# Cymometer.net
KiCad netlist of a schematic drawn in Altium Designer
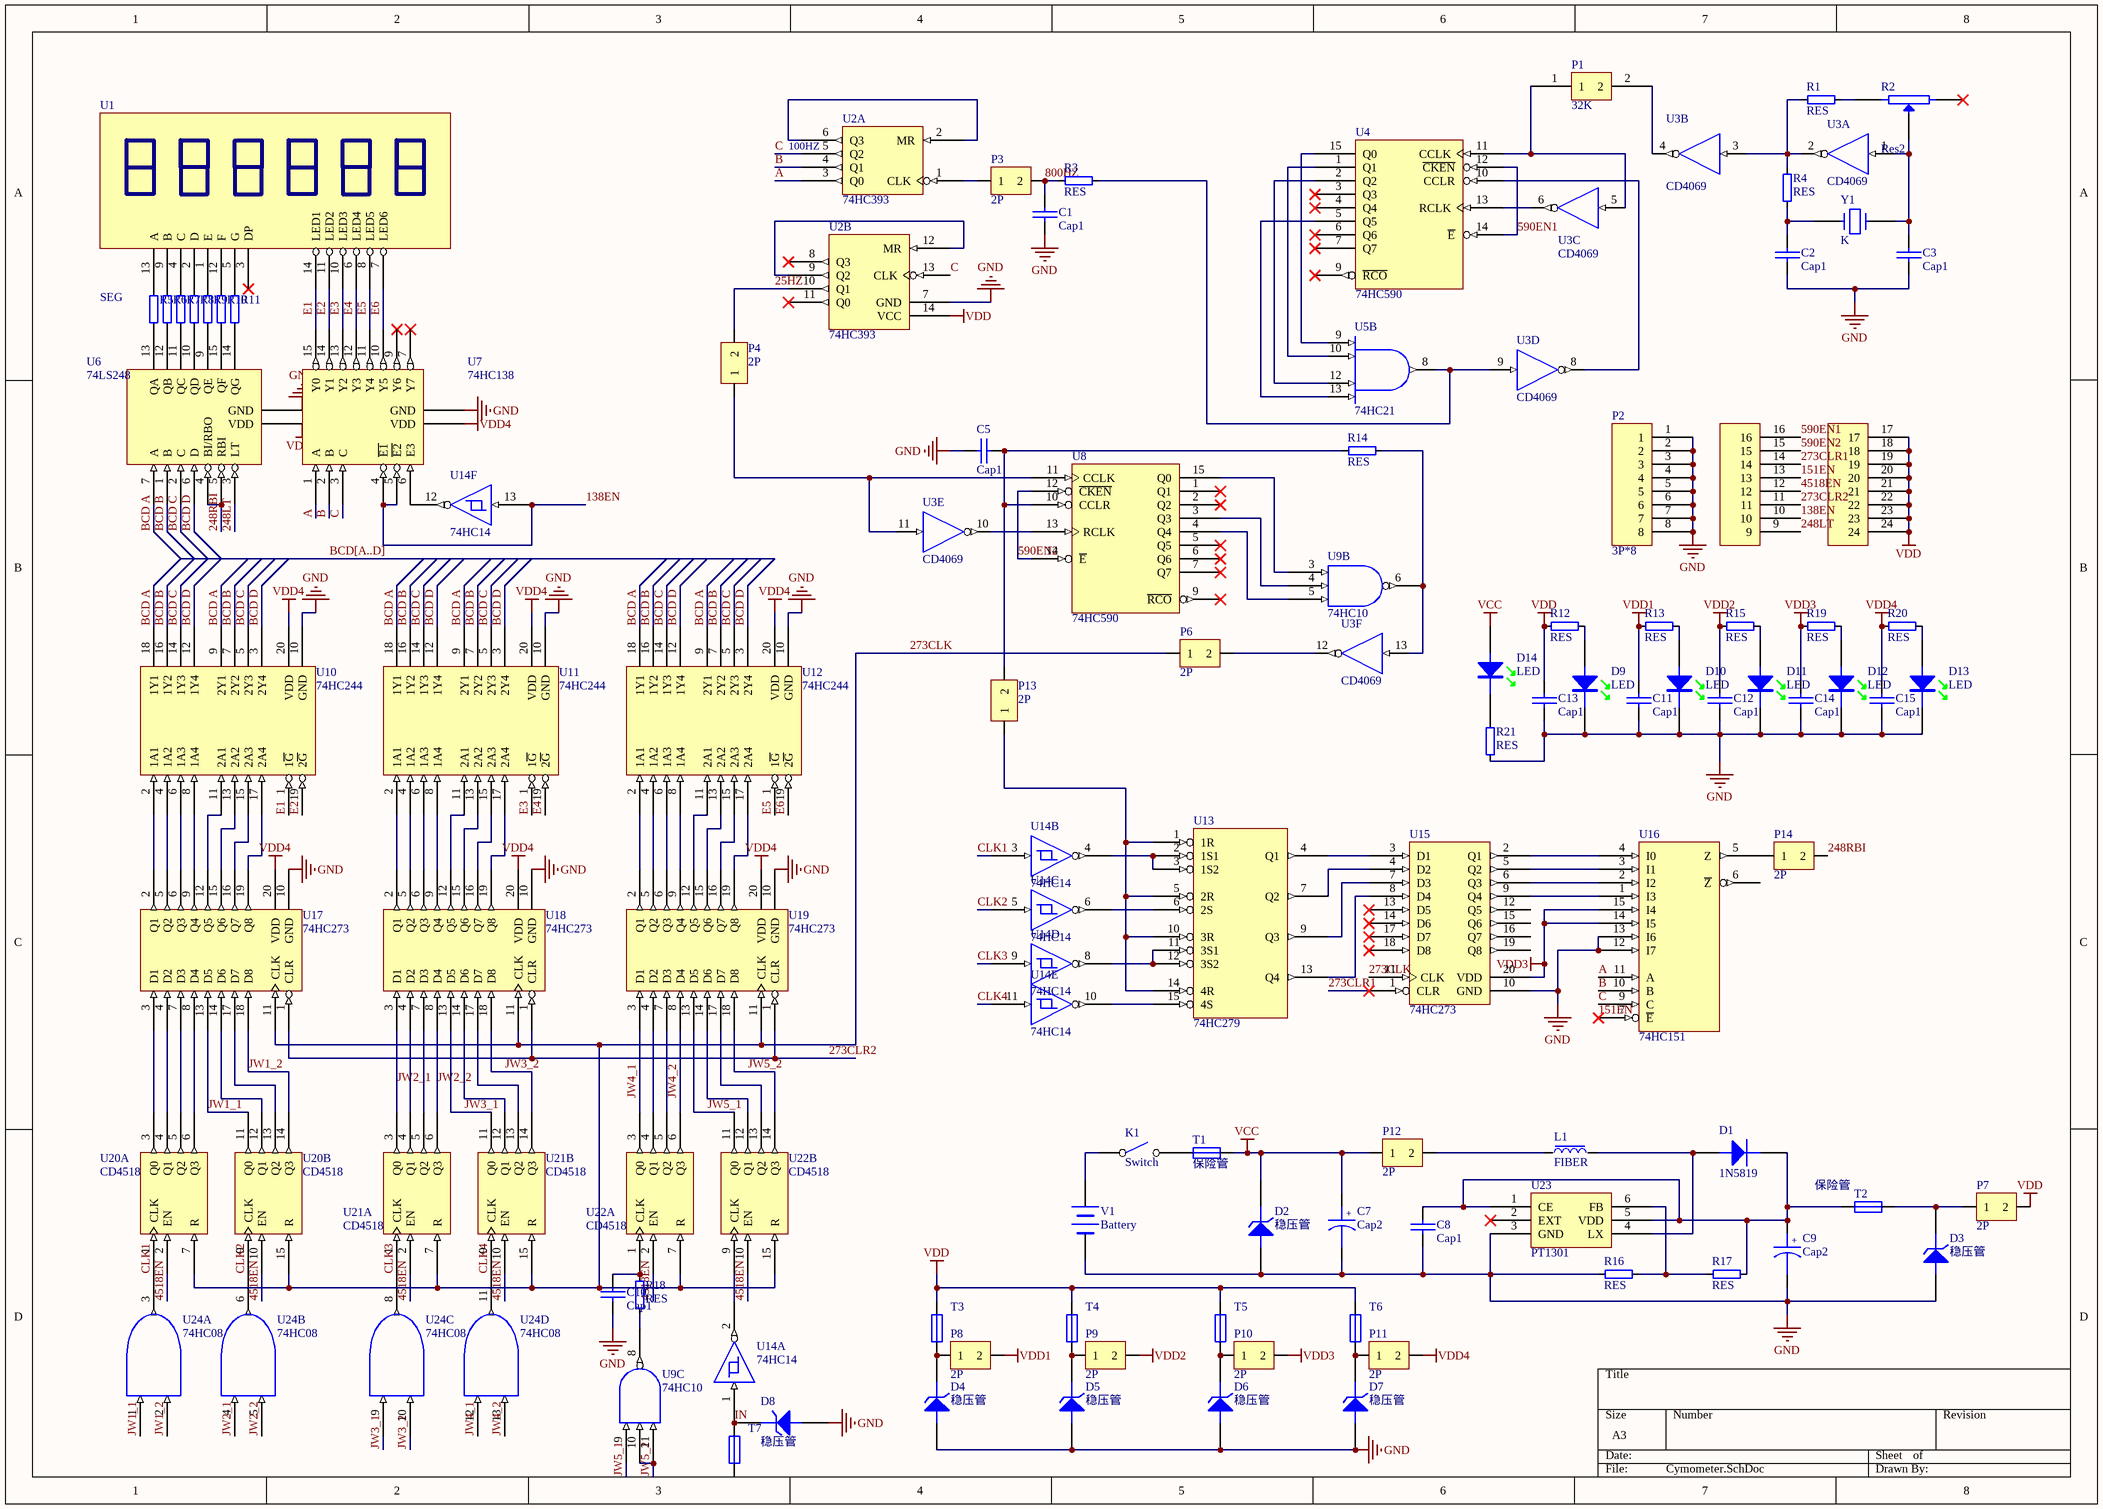
[diagram p0: Cymometer.SchDoc]

(export (version "E")
  (design (tool "Eeschema 10.0.6"))
  (components
    (comp (ref "C1") (value "Cap1") (footprint "Cap1") (libsource (lib "Cymometer") (part "Cap1")))
    (comp (ref "C2") (value "Cap1") (footprint "Cap1") (libsource (lib "Cymometer") (part "Cap1")))
    (comp (ref "C3") (value "Cap1") (footprint "Cap1") (libsource (lib "Cymometer") (part "Cap1")))
    (comp (ref "C5") (value "Cap1") (footprint "Cap1") (libsource (lib "Cymometer") (part "Cap1")))
    (comp (ref "C7") (value "Cap2") (footprint "Cap2") (libsource (lib "Cymometer") (part "Cap2")))
    (comp (ref "C8") (value "Cap1") (footprint "Cap1") (libsource (lib "Cymometer") (part "Cap1")))
    (comp (ref "C9") (value "Cap2") (footprint "Cap2") (libsource (lib "Cymometer") (part "Cap2")))
    (comp (ref "C10") (value "Cap1") (footprint "Cap1") (libsource (lib "Cymometer") (part "Cap1")))
    (comp (ref "C11") (value "Cap1") (footprint "Cap1") (libsource (lib "Cymometer") (part "Cap1")))
    (comp (ref "C12") (value "Cap1") (footprint "Cap1") (libsource (lib "Cymometer") (part "Cap1")))
    (comp (ref "C13") (value "Cap1") (footprint "Cap1") (libsource (lib "Cymometer") (part "Cap1")))
    (comp (ref "C14") (value "Cap1") (footprint "Cap1") (libsource (lib "Cymometer") (part "Cap1")))
    (comp (ref "C15") (value "Cap1") (footprint "Cap1") (libsource (lib "Cymometer") (part "Cap1")))
    (comp (ref "D1") (value "1N5819") (footprint "1N5819(SMA)") (libsource (lib "Cymometer") (part "1N5819")))
    (comp (ref "D2") (value "稳压管") (footprint "1206稳压管") (libsource (lib "Cymometer") (part "稳压管")))
    (comp (ref "D3") (value "稳压管") (footprint "1206稳压管") (libsource (lib "Cymometer") (part "稳压管")))
    (comp (ref "D4") (value "稳压管") (footprint "1206稳压管") (libsource (lib "Cymometer") (part "稳压管")))
    (comp (ref "D5") (value "稳压管") (footprint "1206稳压管") (libsource (lib "Cymometer") (part "稳压管")))
    (comp (ref "D6") (value "稳压管") (footprint "1206稳压管") (libsource (lib "Cymometer") (part "稳压管")))
    (comp (ref "D7") (value "稳压管") (footprint "1206稳压管") (libsource (lib "Cymometer") (part "稳压管")))
    (comp (ref "D8") (value "稳压管") (footprint "1206稳压管") (libsource (lib "Cymometer") (part "稳压管")))
    (comp (ref "D9") (value "LED") (footprint "0805LED") (libsource (lib "Cymometer") (part "LED")))
    (comp (ref "D10") (value "LED") (footprint "0805LED") (libsource (lib "Cymometer") (part "LED")))
    (comp (ref "D11") (value "LED") (footprint "0805LED") (libsource (lib "Cymometer") (part "LED")))
    (comp (ref "D12") (value "LED") (footprint "0805LED") (libsource (lib "Cymometer") (part "LED")))
    (comp (ref "D13") (value "LED") (footprint "0805LED") (libsource (lib "Cymometer") (part "LED")))
    (comp (ref "D14") (value "LED") (footprint "0805LED") (libsource (lib "Cymometer") (part "LED")))
    (comp (ref "K1") (value "Switch") (footprint "Switch") (libsource (lib "Cymometer") (part "Switch")))
    (comp (ref "L1") (value "FIBER") (footprint "FIBER") (libsource (lib "Cymometer") (part "FIBER")))
    (comp (ref "P1") (value "32K") (footprint "2P") (libsource (lib "") (part "2P_2")))
    (comp (ref "P2") (value "3P*8") (footprint "3P*8") (libsource (lib "Cymometer") (part "3P*8")))
    (comp (ref "P3") (value "2P") (footprint "2P") (libsource (lib "Cymometer") (part "2P")))
    (comp (ref "P4") (value "2P") (footprint "2P") (libsource (lib "") (part "2P_1")))
    (comp (ref "P6") (value "2P") (footprint "2P") (libsource (lib "Cymometer") (part "2P")))
    (comp (ref "P7") (value "2P") (footprint "2P") (libsource (lib "Cymometer") (part "2P")))
    (comp (ref "P8") (value "2P") (footprint "2P") (libsource (lib "Cymometer") (part "2P")))
    (comp (ref "P9") (value "2P") (footprint "2P") (libsource (lib "Cymometer") (part "2P")))
    (comp (ref "P10") (value "2P") (footprint "2P") (libsource (lib "Cymometer") (part "2P")))
    (comp (ref "P11") (value "2P") (footprint "2P") (libsource (lib "Cymometer") (part "2P")))
    (comp (ref "P12") (value "2P") (footprint "2P") (libsource (lib "Cymometer") (part "2P")))
    (comp (ref "P13") (value "2P") (footprint "2P") (libsource (lib "") (part "2P_1")))
    (comp (ref "P14") (value "2P") (footprint "2P") (libsource (lib "Cymometer") (part "2P")))
    (comp (ref "R1")
      (value "RES")
      (footprint "0805R")
      (description "电阻")
      (libsource (lib "Cymometer") (part "RES"))
    )
    (comp (ref "R2") (value "Res2") (footprint "Res2") (libsource (lib "Cymometer") (part "Res2")))
    (comp (ref "R3")
      (value "RES")
      (footprint "0805R")
      (description "电阻")
      (libsource (lib "Cymometer") (part "RES"))
    )
    (comp (ref "R4")
      (value "RES")
      (footprint "0805R")
      (description "电阻")
      (libsource (lib "Cymometer") (part "RES"))
    )
    (comp (ref "R5")
      (value "~")
      (footprint "0805R")
      (description "电阻")
      (libsource (lib "Cymometer") (part "RES"))
    )
    (comp (ref "R6")
      (value "~")
      (footprint "0805R")
      (description "电阻")
      (libsource (lib "Cymometer") (part "RES"))
    )
    (comp (ref "R7")
      (value "~")
      (footprint "0805R")
      (description "电阻")
      (libsource (lib "Cymometer") (part "RES"))
    )
    (comp (ref "R8")
      (value "~")
      (footprint "0805R")
      (description "电阻")
      (libsource (lib "Cymometer") (part "RES"))
    )
    (comp (ref "R9")
      (value "~")
      (footprint "0805R")
      (description "电阻")
      (libsource (lib "Cymometer") (part "RES"))
    )
    (comp (ref "R10")
      (value "~")
      (footprint "0805R")
      (description "电阻")
      (libsource (lib "Cymometer") (part "RES"))
    )
    (comp (ref "R11")
      (value "~")
      (footprint "0805R")
      (description "电阻")
      (libsource (lib "Cymometer") (part "RES"))
    )
    (comp (ref "R12")
      (value "RES")
      (footprint "0805R")
      (description "电阻")
      (libsource (lib "Cymometer") (part "RES"))
    )
    (comp (ref "R13")
      (value "RES")
      (footprint "0805R")
      (description "电阻")
      (libsource (lib "Cymometer") (part "RES"))
    )
    (comp (ref "R14")
      (value "RES")
      (footprint "0805R")
      (description "电阻")
      (libsource (lib "Cymometer") (part "RES"))
    )
    (comp (ref "R15")
      (value "RES")
      (footprint "0805R")
      (description "电阻")
      (libsource (lib "Cymometer") (part "RES"))
    )
    (comp (ref "R16")
      (value "RES")
      (footprint "0805R")
      (description "电阻")
      (libsource (lib "Cymometer") (part "RES"))
    )
    (comp (ref "R17")
      (value "RES")
      (footprint "0805R")
      (description "电阻")
      (libsource (lib "Cymometer") (part "RES"))
    )
    (comp (ref "R18")
      (value "RES")
      (footprint "0805R")
      (description "电阻")
      (libsource (lib "Cymometer") (part "RES"))
    )
    (comp (ref "R19")
      (value "RES")
      (footprint "0805R")
      (description "电阻")
      (libsource (lib "Cymometer") (part "RES"))
    )
    (comp (ref "R20")
      (value "RES")
      (footprint "0805R")
      (description "电阻")
      (libsource (lib "Cymometer") (part "RES"))
    )
    (comp (ref "R21")
      (value "RES")
      (footprint "0805R")
      (description "电阻")
      (libsource (lib "Cymometer") (part "RES"))
    )
    (comp (ref "T1") (value "保险管") (footprint "0805T") (libsource (lib "") (part "保险管_1")))
    (comp (ref "T2") (value "保险管") (footprint "0805T") (libsource (lib "") (part "保险管_1")))
    (comp (ref "T3") (value "保险管") (footprint "0805T") (libsource (lib "") (part "保险管_2")))
    (comp (ref "T4") (value "保险管") (footprint "0805T") (libsource (lib "Cymometer") (part "保险管")))
    (comp (ref "T5") (value "保险管") (footprint "0805T") (libsource (lib "") (part "保险管_2")))
    (comp (ref "T6") (value "保险管") (footprint "0805T") (libsource (lib "Cymometer") (part "保险管")))
    (comp (ref "T7") (value "保险管") (footprint "0805T") (libsource (lib "") (part "保险管_2")))
    (comp (ref "U1")
      (value "SEG")
      (footprint "6BIT_SEG")
      (description "数码管")
      (libsource (lib "Cymometer") (part "SEG"))
    )
    (comp (ref "U2") (value "74HC393") (footprint "SOP14") (libsource (lib "Cymometer") (part "74HC393")))
    (comp (ref "U3")
      (value "CD4069")
      (footprint "DIP14")
      (description "CMOS非门")
      (libsource (lib "Cymometer") (part "CD4069"))
    )
    (comp (ref "U4") (value "74HC590") (footprint "SOP16") (libsource (lib "Cymometer") (part "74HC590")))
    (comp (ref "U5")
      (value "74HC21")
      (footprint "SOP14")
      (description "4输入与门")
      (libsource (lib "Cymometer") (part "74HC21"))
    )
    (comp (ref "U6")
      (value "74LS248")
      (footprint "DIP16")
      (description "数码管译码器")
      (libsource (lib "Cymometer") (part "74LS248"))
    )
    (comp (ref "U7")
      (value "74HC138")
      (footprint "SOP16")
      (description "38译码器")
      (libsource (lib "Cymometer") (part "74HC138"))
    )
    (comp (ref "U8") (value "74HC590") (footprint "SOP16") (libsource (lib "") (part "74HC590_1")))
    (comp (ref "U9") (value "74HC10") (footprint "SOP14") (libsource (lib "Cymometer") (part "74HC10")))
    (comp (ref "U10")
      (value "74HC244")
      (footprint "SOP20")
      (description "三态缓冲器")
      (libsource (lib "Cymometer") (part "74HC244"))
    )
    (comp (ref "U11")
      (value "74HC244")
      (footprint "SOP20")
      (description "三态缓冲器")
      (libsource (lib "Cymometer") (part "74HC244"))
    )
    (comp (ref "U12")
      (value "74HC244")
      (footprint "SOP20")
      (description "三态缓冲器")
      (libsource (lib "Cymometer") (part "74HC244"))
    )
    (comp (ref "U13") (value "74HC279") (footprint "DIP16") (libsource (lib "Cymometer") (part "74HC279")))
    (comp (ref "U14") (value "74HC14") (footprint "SOP14") (libsource (lib "Cymometer") (part "74HC14")))
    (comp (ref "U15")
      (value "74HC273")
      (footprint "SOP20")
      (description "D触发器")
      (libsource (lib "") (part "74HC273_1"))
    )
    (comp (ref "U16") (value "74HC151") (footprint "DIP16") (libsource (lib "Cymometer") (part "74HC151")))
    (comp (ref "U17")
      (value "74HC273")
      (footprint "SOP20")
      (description "D触发器")
      (libsource (lib "Cymometer") (part "74HC273"))
    )
    (comp (ref "U18")
      (value "74HC273")
      (footprint "SOP20")
      (description "D触发器")
      (libsource (lib "Cymometer") (part "74HC273"))
    )
    (comp (ref "U19")
      (value "74HC273")
      (footprint "SOP20")
      (description "D触发器")
      (libsource (lib "Cymometer") (part "74HC273"))
    )
    (comp (ref "U20")
      (value "CD4518")
      (footprint "DIP16")
      (description "BCD计数器")
      (libsource (lib "Cymometer") (part "CD4518"))
    )
    (comp (ref "U21")
      (value "CD4518")
      (footprint "DIP16")
      (description "BCD计数器")
      (libsource (lib "") (part "CD4518_1"))
    )
    (comp (ref "U22")
      (value "CD4518")
      (footprint "DIP16")
      (description "BCD计数器")
      (libsource (lib "") (part "CD4518_1"))
    )
    (comp (ref "U23") (value "PT1301") (footprint "Sop26") (libsource (lib "Cymometer") (part "PT1301")))
    (comp (ref "U24")
      (value "74HC08")
      (footprint "SOP14")
      (description "二输入与门")
      (libsource (lib "Cymometer") (part "74HC08"))
    )
    (comp (ref "V1") (value "Battery") (footprint "Battry") (libsource (lib "Cymometer") (part "Battery")))
    (comp (ref "Y1")
      (value "K")
      (footprint "CRYSTAL")
      (description "晶振")
      (libsource (lib "Cymometer") (part "CRYSTAL"))
    )
  )
  (nets
    (net (code "2") (name "/25HZ") (class "Default")
      (node (ref "P4") (pin "2") (pinfunction "2_2") (pintype "passive"))
      (node (ref "U2") (pin "10") (pinfunction "Q1_10") (pintype "output"))
    )
    (net (code "3") (name "/138EN") (class "Default")
      (node (ref "P2") (pin "10") (pinfunction "10_10") (pintype "passive"))
      (node (ref "U14") (pin "13") (pintype "input"))
      (node (ref "U7") (pin "4") (pinfunction "~{E1}_4") (pintype "input"))
      (node (ref "U7") (pin "5") (pinfunction "~{E2}_5") (pintype "input"))
    )
    (net (code "4") (name "/151EN") (class "Default")
      (node (ref "P2") (pin "13") (pinfunction "13_13") (pintype "passive"))
      (node (ref "U16") (pin "7") (pinfunction "~{E}_7") (pintype "input"))
    )
    (net (code "5") (name "/248LT") (class "Default")
      (node (ref "P2") (pin "9") (pinfunction "9_9") (pintype "passive"))
      (node (ref "U6") (pin "3") (pinfunction "LT_3") (pintype "input"))
    )
    (net (code "6") (name "/248RBI") (class "Default")
      (node (ref "P14") (pin "2") (pinfunction "2_2") (pintype "passive"))
      (node (ref "U6") (pin "4") (pinfunction "BI/RBO_4") (pintype "input"))
      (node (ref "U6") (pin "5") (pinfunction "RBI_5") (pintype "input"))
    )
    (net (code "7") (name "/273CLK") (class "Default")
      (node (ref "P6") (pin "1") (pinfunction "1_1") (pintype "passive"))
      (node (ref "U15") (pin "11") (pinfunction "CLK_11") (pintype "input"))
      (node (ref "U17") (pin "11") (pinfunction "CLK_11") (pintype "input"))
      (node (ref "U18") (pin "11") (pinfunction "CLK_11") (pintype "input"))
      (node (ref "U19") (pin "11") (pinfunction "CLK_11") (pintype "input"))
      (node (ref "U20") (pin "15") (pinfunction "R_15") (pintype "input"))
      (node (ref "U20") (pin "7") (pinfunction "R_7") (pintype "input"))
      (node (ref "U21") (pin "15") (pinfunction "R_15") (pintype "input"))
      (node (ref "U21") (pin "7") (pinfunction "R_7") (pintype "input"))
      (node (ref "U22") (pin "15") (pinfunction "R_15") (pintype "input"))
      (node (ref "U22") (pin "7") (pinfunction "R_7") (pintype "input"))
    )
    (net (code "8") (name "/273CLR1") (class "Default")
      (node (ref "P2") (pin "14") (pinfunction "14_14") (pintype "passive"))
      (node (ref "U15") (pin "1") (pinfunction "CLR_1") (pintype "input"))
    )
    (net (code "9") (name "/273CLR2") (class "Default")
      (node (ref "P2") (pin "11") (pinfunction "11_11") (pintype "passive"))
      (node (ref "U17") (pin "1") (pinfunction "CLR_1") (pintype "input"))
      (node (ref "U18") (pin "1") (pinfunction "CLR_1") (pintype "input"))
      (node (ref "U19") (pin "1") (pinfunction "CLR_1") (pintype "input"))
    )
    (net (code "10") (name "/590EN1") (class "Default")
      (node (ref "P2") (pin "16") (pinfunction "16_16") (pintype "passive"))
      (node (ref "U4") (pin "12") (pinfunction "~{CKEN}_12") (pintype "input"))
      (node (ref "U4") (pin "14") (pinfunction "~{E}_14") (pintype "input"))
    )
    (net (code "11") (name "/590EN2") (class "Default")
      (node (ref "P2") (pin "15") (pinfunction "15_15") (pintype "passive"))
      (node (ref "U8") (pin "12") (pinfunction "~{CKEN}_12") (pintype "input"))
      (node (ref "U8") (pin "14") (pinfunction "~{E}_14") (pintype "input"))
    )
    (net (code "12") (name "/800HZ") (class "Default")
      (node (ref "C1") (pin "2") (pinfunction "2_2") (pintype "passive"))
      (node (ref "P3") (pin "2") (pinfunction "2_2") (pintype "passive"))
      (node (ref "R3") (pin "1") (pinfunction "1_1") (pintype "passive"))
    )
    (net (code "13") (name "/4518EN") (class "Default")
      (node (ref "P2") (pin "12") (pinfunction "12_12") (pintype "passive"))
      (node (ref "U20") (pin "10") (pinfunction "EN_10") (pintype "input"))
      (node (ref "U20") (pin "2") (pinfunction "EN_2") (pintype "input"))
      (node (ref "U21") (pin "10") (pinfunction "EN_10") (pintype "input"))
      (node (ref "U21") (pin "2") (pinfunction "EN_2") (pintype "input"))
      (node (ref "U22") (pin "10") (pinfunction "EN_10") (pintype "input"))
      (node (ref "U22") (pin "2") (pinfunction "EN_2") (pintype "input"))
    )
    (net (code "14") (name "/A") (class "Default")
      (node (ref "U16") (pin "11") (pinfunction "A_11") (pintype "input"))
      (node (ref "U2") (pin "3") (pinfunction "Q0_3") (pintype "output"))
      (node (ref "U7") (pin "1") (pinfunction "A_1") (pintype "input"))
    )
    (net (code "15") (name "/B") (class "Default")
      (node (ref "U16") (pin "10") (pinfunction "B_10") (pintype "input"))
      (node (ref "U2") (pin "4") (pinfunction "Q1_4") (pintype "output"))
      (node (ref "U7") (pin "2") (pinfunction "B_2") (pintype "input"))
    )
    (net (code "16") (name "/BCD A") (class "Default")
      (node (ref "U10") (pin "18") (pinfunction "1Y1_18") (pintype "tri_state"))
      (node (ref "U10") (pin "9") (pinfunction "2Y1_9") (pintype "tri_state"))
      (node (ref "U11") (pin "18") (pinfunction "1Y1_18") (pintype "tri_state"))
      (node (ref "U11") (pin "9") (pinfunction "2Y1_9") (pintype "tri_state"))
      (node (ref "U12") (pin "18") (pinfunction "1Y1_18") (pintype "tri_state"))
      (node (ref "U12") (pin "9") (pinfunction "2Y1_9") (pintype "tri_state"))
      (node (ref "U6") (pin "7") (pinfunction "A_7") (pintype "input"))
    )
    (net (code "17") (name "/BCD B") (class "Default")
      (node (ref "U10") (pin "16") (pinfunction "1Y2_16") (pintype "tri_state"))
      (node (ref "U10") (pin "7") (pinfunction "2Y2_7") (pintype "tri_state"))
      (node (ref "U11") (pin "16") (pinfunction "1Y2_16") (pintype "tri_state"))
      (node (ref "U11") (pin "7") (pinfunction "2Y2_7") (pintype "tri_state"))
      (node (ref "U12") (pin "16") (pinfunction "1Y2_16") (pintype "tri_state"))
      (node (ref "U12") (pin "7") (pinfunction "2Y2_7") (pintype "tri_state"))
      (node (ref "U6") (pin "1") (pinfunction "B_1") (pintype "input"))
    )
    (net (code "18") (name "/BCD C") (class "Default")
      (node (ref "U10") (pin "14") (pinfunction "1Y3_14") (pintype "tri_state"))
      (node (ref "U10") (pin "5") (pinfunction "2Y3_5") (pintype "tri_state"))
      (node (ref "U11") (pin "14") (pinfunction "1Y3_14") (pintype "tri_state"))
      (node (ref "U11") (pin "5") (pinfunction "2Y3_5") (pintype "tri_state"))
      (node (ref "U12") (pin "14") (pinfunction "1Y3_14") (pintype "tri_state"))
      (node (ref "U12") (pin "5") (pinfunction "2Y3_5") (pintype "tri_state"))
      (node (ref "U6") (pin "2") (pinfunction "C_2") (pintype "input"))
    )
    (net (code "19") (name "/BCD D") (class "Default")
      (node (ref "U10") (pin "12") (pinfunction "1Y4_12") (pintype "tri_state"))
      (node (ref "U10") (pin "3") (pinfunction "2Y4_3") (pintype "tri_state"))
      (node (ref "U11") (pin "12") (pinfunction "1Y4_12") (pintype "tri_state"))
      (node (ref "U11") (pin "3") (pinfunction "2Y4_3") (pintype "tri_state"))
      (node (ref "U12") (pin "12") (pinfunction "1Y4_12") (pintype "tri_state"))
      (node (ref "U12") (pin "3") (pinfunction "2Y4_3") (pintype "tri_state"))
      (node (ref "U6") (pin "6") (pinfunction "D_6") (pintype "input"))
    )
    (net (code "20") (name "/C") (class "Default")
      (node (ref "U16") (pin "9") (pinfunction "C_9") (pintype "input"))
      (node (ref "U2") (pin "13") (pinfunction "CLK_13") (pintype "input"))
      (node (ref "U2") (pin "5") (pinfunction "Q2_5") (pintype "output"))
      (node (ref "U7") (pin "3") (pinfunction "C_3") (pintype "input"))
    )
    (net (code "21") (name "/CLK1") (class "Default")
      (node (ref "U14") (pin "3") (pintype "input"))
      (node (ref "U20") (pin "1") (pinfunction "CLK_1") (pintype "input"))
      (node (ref "U24") (pin "3") (pintype "output"))
    )
    (net (code "22") (name "/CLK2") (class "Default")
      (node (ref "U14") (pin "5") (pintype "input"))
      (node (ref "U20") (pin "9") (pinfunction "CLK_9") (pintype "input"))
      (node (ref "U24") (pin "6") (pintype "output"))
    )
    (net (code "23") (name "/CLK3") (class "Default")
      (node (ref "U14") (pin "9") (pintype "input"))
      (node (ref "U21") (pin "1") (pinfunction "CLK_1") (pintype "input"))
      (node (ref "U24") (pin "8") (pintype "output"))
    )
    (net (code "24") (name "/CLK4") (class "Default")
      (node (ref "U14") (pin "11") (pintype "input"))
      (node (ref "U21") (pin "9") (pinfunction "CLK_9") (pintype "input"))
      (node (ref "U24") (pin "11") (pintype "output"))
    )
    (net (code "25") (name "/E1") (class "Default")
      (node (ref "U1") (pin "14") (pinfunction "LED1_14") (pintype "passive"))
      (node (ref "U10") (pin "1") (pinfunction "1~{G}_1") (pintype "input"))
      (node (ref "U7") (pin "15") (pinfunction "Y0_15") (pintype "output"))
    )
    (net (code "26") (name "/E2") (class "Default")
      (node (ref "U1") (pin "11") (pinfunction "LED2_11") (pintype "passive"))
      (node (ref "U10") (pin "19") (pinfunction "2~{G}_19") (pintype "input"))
      (node (ref "U7") (pin "14") (pinfunction "Y1_14") (pintype "output"))
    )
    (net (code "27") (name "/E3") (class "Default")
      (node (ref "U1") (pin "10") (pinfunction "LED3_10") (pintype "passive"))
      (node (ref "U11") (pin "1") (pinfunction "1~{G}_1") (pintype "input"))
      (node (ref "U7") (pin "13") (pinfunction "Y2_13") (pintype "output"))
    )
    (net (code "28") (name "/E4") (class "Default")
      (node (ref "U1") (pin "6") (pinfunction "LED4_6") (pintype "passive"))
      (node (ref "U11") (pin "19") (pinfunction "2~{G}_19") (pintype "input"))
      (node (ref "U7") (pin "12") (pinfunction "Y3_12") (pintype "output"))
    )
    (net (code "29") (name "/E5") (class "Default")
      (node (ref "U1") (pin "8") (pinfunction "LED5_8") (pintype "passive"))
      (node (ref "U12") (pin "1") (pinfunction "1~{G}_1") (pintype "input"))
      (node (ref "U7") (pin "11") (pinfunction "Y4_11") (pintype "output"))
    )
    (net (code "30") (name "/E6") (class "Default")
      (node (ref "U1") (pin "7") (pinfunction "LED6_7") (pintype "passive"))
      (node (ref "U12") (pin "19") (pinfunction "2~{G}_19") (pintype "input"))
      (node (ref "U7") (pin "10") (pinfunction "Y5_10") (pintype "output"))
    )
    (net (code "31") (name "/IN") (class "Default")
      (node (ref "D8") (pin "K") (pinfunction "K_K") (pintype "passive"))
      (node (ref "T7") (pin "1") (pinfunction "1_1") (pintype "passive"))
      (node (ref "U14") (pin "1") (pintype "input"))
    )
    (net (code "32") (name "/JW1_1") (class "Default")
      (node (ref "U17") (pin "13") (pinfunction "D5_13") (pintype "input"))
      (node (ref "U20") (pin "11") (pinfunction "Q0_11") (pintype "output"))
      (node (ref "U24") (pin "1") (pintype "input"))
    )
    (net (code "33") (name "/JW1_2") (class "Default")
      (node (ref "U17") (pin "18") (pinfunction "D8_18") (pintype "input"))
      (node (ref "U20") (pin "14") (pinfunction "Q3_14") (pintype "output"))
      (node (ref "U24") (pin "2") (pintype "input"))
    )
    (net (code "34") (name "/JW2_1") (class "Default")
      (node (ref "U18") (pin "3") (pinfunction "D1_3") (pintype "input"))
      (node (ref "U21") (pin "3") (pinfunction "Q0_3") (pintype "output"))
      (node (ref "U24") (pin "4") (pintype "input"))
    )
    (net (code "35") (name "/JW2_2") (class "Default")
      (node (ref "U18") (pin "8") (pinfunction "D4_8") (pintype "input"))
      (node (ref "U21") (pin "6") (pinfunction "Q3_6") (pintype "output"))
      (node (ref "U24") (pin "5") (pintype "input"))
    )
    (net (code "36") (name "/JW3_1") (class "Default")
      (node (ref "U18") (pin "13") (pinfunction "D5_13") (pintype "input"))
      (node (ref "U21") (pin "11") (pinfunction "Q0_11") (pintype "output"))
      (node (ref "U24") (pin "9") (pintype "input"))
    )
    (net (code "37") (name "/JW3_2") (class "Default")
      (node (ref "U18") (pin "18") (pinfunction "D8_18") (pintype "input"))
      (node (ref "U21") (pin "14") (pinfunction "Q3_14") (pintype "output"))
      (node (ref "U24") (pin "10") (pintype "input"))
    )
    (net (code "38") (name "/JW4_1") (class "Default")
      (node (ref "U19") (pin "3") (pinfunction "D1_3") (pintype "input"))
      (node (ref "U22") (pin "3") (pinfunction "Q0_3") (pintype "output"))
      (node (ref "U24") (pin "12") (pintype "input"))
    )
    (net (code "39") (name "/JW4_2") (class "Default")
      (node (ref "U19") (pin "8") (pinfunction "D4_8") (pintype "input"))
      (node (ref "U22") (pin "6") (pinfunction "Q3_6") (pintype "output"))
      (node (ref "U24") (pin "13") (pintype "input"))
    )
    (net (code "40") (name "/JW5_1") (class "Default")
      (node (ref "U19") (pin "13") (pinfunction "D5_13") (pintype "input"))
      (node (ref "U22") (pin "11") (pinfunction "Q0_11") (pintype "output"))
      (node (ref "U9") (pin "9") (pintype "input"))
    )
    (net (code "41") (name "/JW5_2") (class "Default")
      (node (ref "U19") (pin "18") (pinfunction "D8_18") (pintype "input"))
      (node (ref "U22") (pin "14") (pinfunction "Q3_14") (pintype "output"))
      (node (ref "U9") (pin "10") (pintype "input"))
      (node (ref "U9") (pin "11") (pintype "input"))
    )
    (net (code "43") (name "GND") (class "Default")
      (node (ref "C1") (pin "1") (pinfunction "1_1") (pintype "passive"))
      (node (ref "C10") (pin "1") (pinfunction "1_1") (pintype "passive"))
      (node (ref "C11") (pin "1") (pinfunction "1_1") (pintype "passive"))
      (node (ref "C12") (pin "1") (pinfunction "1_1") (pintype "passive"))
      (node (ref "C13") (pin "1") (pinfunction "1_1") (pintype "passive"))
      (node (ref "C14") (pin "1") (pinfunction "1_1") (pintype "passive"))
      (node (ref "C15") (pin "1") (pinfunction "1_1") (pintype "passive"))
      (node (ref "C2") (pin "1") (pinfunction "1_1") (pintype "passive"))
      (node (ref "C3") (pin "1") (pinfunction "1_1") (pintype "passive"))
      (node (ref "C5") (pin "2") (pinfunction "2_2") (pintype "passive"))
      (node (ref "C7") (pin "K") (pinfunction "2_K") (pintype "passive"))
      (node (ref "C8") (pin "1") (pinfunction "1_1") (pintype "passive"))
      (node (ref "C9") (pin "K") (pinfunction "2_K") (pintype "passive"))
      (node (ref "D10") (pin "K") (pinfunction "2_K") (pintype "passive"))
      (node (ref "D11") (pin "K") (pinfunction "2_K") (pintype "passive"))
      (node (ref "D12") (pin "K") (pinfunction "2_K") (pintype "passive"))
      (node (ref "D13") (pin "K") (pinfunction "2_K") (pintype "passive"))
      (node (ref "D2") (pin "A") (pinfunction "A_A") (pintype "passive"))
      (node (ref "D3") (pin "A") (pinfunction "A_A") (pintype "passive"))
      (node (ref "D4") (pin "A") (pinfunction "A_A") (pintype "passive"))
      (node (ref "D5") (pin "A") (pinfunction "A_A") (pintype "passive"))
      (node (ref "D6") (pin "A") (pinfunction "A_A") (pintype "passive"))
      (node (ref "D7") (pin "A") (pinfunction "A_A") (pintype "passive"))
      (node (ref "D8") (pin "A") (pinfunction "A_A") (pintype "passive"))
      (node (ref "D9") (pin "K") (pinfunction "2_K") (pintype "passive"))
      (node (ref "P2") (pin "1") (pinfunction "1_1") (pintype "passive"))
      (node (ref "P2") (pin "2") (pinfunction "2_2") (pintype "passive"))
      (node (ref "P2") (pin "3") (pinfunction "3_3") (pintype "passive"))
      (node (ref "P2") (pin "4") (pinfunction "4_4") (pintype "passive"))
      (node (ref "P2") (pin "5") (pinfunction "5_5") (pintype "passive"))
      (node (ref "P2") (pin "6") (pinfunction "6_6") (pintype "passive"))
      (node (ref "P2") (pin "7") (pinfunction "7_7") (pintype "passive"))
      (node (ref "P2") (pin "8") (pinfunction "8_8") (pintype "passive"))
      (node (ref "R16") (pin "1") (pinfunction "1_1") (pintype "passive"))
      (node (ref "R21") (pin "2") (pinfunction "2_2") (pintype "passive"))
      (node (ref "U10") (pin "10") (pinfunction "GND_10") (pintype "power_in"))
      (node (ref "U11") (pin "10") (pinfunction "GND_10") (pintype "power_in"))
      (node (ref "U12") (pin "10") (pinfunction "GND_10") (pintype "power_in"))
      (node (ref "U15") (pin "10") (pinfunction "GND_10") (pintype "power_in"))
      (node (ref "U16") (pin "12") (pinfunction "I7_12") (pintype "input"))
      (node (ref "U16") (pin "13") (pinfunction "I6_13") (pintype "input"))
      (node (ref "U17") (pin "10") (pinfunction "GND_10") (pintype "power_in"))
      (node (ref "U18") (pin "10") (pinfunction "GND_10") (pintype "power_in"))
      (node (ref "U19") (pin "10") (pinfunction "GND_10") (pintype "power_in"))
      (node (ref "U2") (pin "7") (pinfunction "GND_7") (pintype "power_in"))
      (node (ref "U23") (pin "3") (pinfunction "GND_3") (pintype "passive"))
      (node (ref "U6") (pin "8") (pinfunction "GND_8") (pintype "power_in"))
      (node (ref "U7") (pin "8") (pinfunction "GND_8") (pintype "power_in"))
      (node (ref "V1") (pin "2") (pinfunction "-_2") (pintype "passive"))
    )
    (net (code "44") (name "Net-(C2-Pad2)") (class "Default")
      (node (ref "C2") (pin "2") (pinfunction "2_2") (pintype "passive"))
      (node (ref "R4") (pin "1") (pinfunction "1_1") (pintype "passive"))
      (node (ref "Y1") (pin "1") (pinfunction "1_1") (pintype "passive"))
    )
    (net (code "45") (name "Net-(C9-1)") (class "Default")
      (node (ref "C8") (pin "2") (pinfunction "2_2") (pintype "passive"))
      (node (ref "C9") (pin "A") (pinfunction "1_A") (pintype "passive"))
      (node (ref "D1") (pin "K") (pinfunction "K_K") (pintype "passive"))
      (node (ref "R17") (pin "2") (pinfunction "2_2") (pintype "passive"))
      (node (ref "T2") (pin "1") (pinfunction "1_1") (pintype "passive"))
      (node (ref "U23") (pin "1") (pinfunction "CE_1") (pintype "passive"))
      (node (ref "U23") (pin "5") (pinfunction "VDD_5") (pintype "passive"))
    )
    (net (code "46") (name "Net-(D3-PadK)") (class "Default")
      (node (ref "D3") (pin "K") (pinfunction "K_K") (pintype "passive"))
      (node (ref "P7") (pin "1") (pinfunction "1_1") (pintype "passive"))
      (node (ref "T2") (pin "2") (pinfunction "2_2") (pintype "passive"))
    )
    (net (code "47") (name "Net-(D4-PadK)") (class "Default")
      (node (ref "D4") (pin "K") (pinfunction "K_K") (pintype "passive"))
      (node (ref "P8") (pin "1") (pinfunction "1_1") (pintype "passive"))
      (node (ref "T3") (pin "2") (pinfunction "2_2") (pintype "passive"))
    )
    (net (code "48") (name "Net-(D5-PadK)") (class "Default")
      (node (ref "D5") (pin "K") (pinfunction "K_K") (pintype "passive"))
      (node (ref "P9") (pin "1") (pinfunction "1_1") (pintype "passive"))
      (node (ref "T4") (pin "1") (pinfunction "1_1") (pintype "passive"))
    )
    (net (code "49") (name "Net-(D6-PadK)") (class "Default")
      (node (ref "D6") (pin "K") (pinfunction "K_K") (pintype "passive"))
      (node (ref "P10") (pin "1") (pinfunction "1_1") (pintype "passive"))
      (node (ref "T5") (pin "2") (pinfunction "2_2") (pintype "passive"))
    )
    (net (code "50") (name "Net-(D7-PadK)") (class "Default")
      (node (ref "D7") (pin "K") (pinfunction "K_K") (pintype "passive"))
      (node (ref "P11") (pin "1") (pinfunction "1_1") (pintype "passive"))
      (node (ref "T6") (pin "1") (pinfunction "1_1") (pintype "passive"))
    )
    (net (code "51") (name "Net-(D9-1)") (class "Default")
      (node (ref "D9") (pin "A") (pinfunction "1_A") (pintype "passive"))
      (node (ref "R12") (pin "1") (pinfunction "1_1") (pintype "passive"))
    )
    (net (code "52") (name "Net-(D10-1)") (class "Default")
      (node (ref "D10") (pin "A") (pinfunction "1_A") (pintype "passive"))
      (node (ref "R13") (pin "1") (pinfunction "1_1") (pintype "passive"))
    )
    (net (code "53") (name "Net-(D11-1)") (class "Default")
      (node (ref "D11") (pin "A") (pinfunction "1_A") (pintype "passive"))
      (node (ref "R15") (pin "1") (pinfunction "1_1") (pintype "passive"))
    )
    (net (code "54") (name "Net-(D12-1)") (class "Default")
      (node (ref "D12") (pin "A") (pinfunction "1_A") (pintype "passive"))
      (node (ref "R19") (pin "1") (pinfunction "1_1") (pintype "passive"))
    )
    (net (code "55") (name "Net-(D13-1)") (class "Default")
      (node (ref "D13") (pin "A") (pinfunction "1_A") (pintype "passive"))
      (node (ref "R20") (pin "1") (pinfunction "1_1") (pintype "passive"))
    )
    (net (code "56") (name "Net-(D14-2)") (class "Default")
      (node (ref "D14") (pin "K") (pinfunction "2_K") (pintype "passive"))
      (node (ref "R21") (pin "1") (pinfunction "1_1") (pintype "passive"))
    )
    (net (code "57") (name "Net-(K1-Pad2)") (class "Default")
      (node (ref "K1") (pin "2") (pinfunction "2_2") (pintype "passive"))
      (node (ref "T1") (pin "1") (pinfunction "1_1") (pintype "passive"))
    )
    (net (code "58") (name "Net-(L1-Pad1)") (class "Default")
      (node (ref "L1") (pin "1") (pintype "passive"))
      (node (ref "P12") (pin "2") (pinfunction "2_2") (pintype "passive"))
    )
    (net (code "59") (name "Net-(R1-Pad1)") (class "Default")
      (node (ref "R1") (pin "1") (pinfunction "1_1") (pintype "passive"))
      (node (ref "R2") (pin "2") (pinfunction "2_2") (pintype "passive"))
    )
    (net (code "60") (name "Net-(R2-W)") (class "Default")
      (node (ref "C3") (pin "2") (pinfunction "2_2") (pintype "passive"))
      (node (ref "R2") (pin "3") (pinfunction "W_3") (pintype "passive"))
      (node (ref "U3") (pin "1") (pinfunction "A_1") (pintype "input"))
      (node (ref "Y1") (pin "2") (pinfunction "2_2") (pintype "passive"))
    )
    (net (code "61") (name "Net-(R18-Pad1)") (class "Default")
      (node (ref "R18") (pin "1") (pinfunction "1_1") (pintype "passive"))
      (node (ref "U9") (pin "8") (pintype "output"))
    )
    (net (code "62") (name "Net-(U1-A)") (class "Default")
      (node (ref "R5") (pin "2") (pinfunction "2_2") (pintype "passive"))
      (node (ref "U1") (pin "13") (pinfunction "A_13") (pintype "passive"))
    )
    (net (code "63") (name "Net-(U1-B)") (class "Default")
      (node (ref "R6") (pin "2") (pinfunction "2_2") (pintype "passive"))
      (node (ref "U1") (pin "9") (pinfunction "B_9") (pintype "passive"))
    )
    (net (code "64") (name "Net-(U1-C)") (class "Default")
      (node (ref "R7") (pin "2") (pinfunction "2_2") (pintype "passive"))
      (node (ref "U1") (pin "4") (pinfunction "C_4") (pintype "passive"))
    )
    (net (code "65") (name "Net-(U1-D)") (class "Default")
      (node (ref "R8") (pin "2") (pinfunction "2_2") (pintype "passive"))
      (node (ref "U1") (pin "2") (pinfunction "D_2") (pintype "passive"))
    )
    (net (code "66") (name "Net-(U1-E)") (class "Default")
      (node (ref "R9") (pin "2") (pinfunction "2_2") (pintype "passive"))
      (node (ref "U1") (pin "1") (pinfunction "E_1") (pintype "passive"))
    )
    (net (code "67") (name "Net-(U1-F)") (class "Default")
      (node (ref "R10") (pin "2") (pinfunction "2_2") (pintype "passive"))
      (node (ref "U1") (pin "12") (pinfunction "F_12") (pintype "passive"))
    )
    (net (code "68") (name "Net-(U1-G)") (class "Default")
      (node (ref "R11") (pin "2") (pinfunction "2_2") (pintype "passive"))
      (node (ref "U1") (pin "5") (pinfunction "G_5") (pintype "passive"))
    )
    (net (code "69") (name "Net-(U2A-CLK)") (class "Default")
      (node (ref "P3") (pin "1") (pinfunction "1_1") (pintype "passive"))
      (node (ref "U2") (pin "1") (pinfunction "CLK_1") (pintype "input"))
    )
    (net (code "70") (name "Net-(U2A-MR)") (class "Default")
      (node (ref "U2") (pin "2") (pinfunction "MR_2") (pintype "input"))
      (node (ref "U2") (pin "6") (pinfunction "Q3_6") (pintype "output"))
    )
    (net (code "71") (name "Net-(U2B-MR)") (class "Default")
      (node (ref "U2") (pin "12") (pinfunction "MR_12") (pintype "input"))
      (node (ref "U2") (pin "9") (pinfunction "Q2_9") (pintype "output"))
    )
    (net (code "72") (name "Net-(U3A-Y)") (class "Default")
      (node (ref "R1") (pin "2") (pinfunction "2_2") (pintype "passive"))
      (node (ref "R4") (pin "2") (pinfunction "2_2") (pintype "passive"))
      (node (ref "U3") (pin "2") (pinfunction "Y_2") (pintype "output"))
      (node (ref "U3") (pin "3") (pinfunction "A_3") (pintype "input"))
    )
    (net (code "73") (name "Net-(U3B-Y)") (class "Default")
      (node (ref "P1") (pin "2") (pinfunction "2_2") (pintype "passive"))
      (node (ref "U3") (pin "4") (pinfunction "Y_4") (pintype "output"))
    )
    (net (code "74") (name "Net-(U3C-A)") (class "Default")
      (node (ref "P1") (pin "1") (pinfunction "1_1") (pintype "passive"))
      (node (ref "U3") (pin "5") (pinfunction "A_5") (pintype "input"))
      (node (ref "U4") (pin "11") (pinfunction "CCLK_11") (pintype "input"))
    )
    (net (code "75") (name "Net-(U3C-Y)") (class "Default")
      (node (ref "U3") (pin "6") (pinfunction "Y_6") (pintype "output"))
      (node (ref "U4") (pin "13") (pinfunction "RCLK_13") (pintype "input"))
    )
    (net (code "76") (name "Net-(U3D-A)") (class "Default")
      (node (ref "R3") (pin "2") (pinfunction "2_2") (pintype "passive"))
      (node (ref "U3") (pin "9") (pinfunction "A_9") (pintype "input"))
      (node (ref "U5") (pin "8") (pinfunction "Y_8") (pintype "output"))
    )
    (net (code "77") (name "Net-(U3D-Y)") (class "Default")
      (node (ref "U3") (pin "8") (pinfunction "Y_8") (pintype "output"))
      (node (ref "U4") (pin "10") (pinfunction "CCLR_10") (pintype "input"))
    )
    (net (code "78") (name "Net-(U3E-A)") (class "Default")
      (node (ref "P4") (pin "1") (pinfunction "1_1") (pintype "passive"))
      (node (ref "U3") (pin "11") (pinfunction "A_11") (pintype "input"))
      (node (ref "U8") (pin "11") (pinfunction "CCLK_11") (pintype "input"))
    )
    (net (code "79") (name "Net-(U3E-Y)") (class "Default")
      (node (ref "U3") (pin "10") (pinfunction "Y_10") (pintype "output"))
      (node (ref "U8") (pin "13") (pinfunction "RCLK_13") (pintype "input"))
    )
    (net (code "80") (name "Net-(U3F-A)") (class "Default")
      (node (ref "R14") (pin "2") (pinfunction "2_2") (pintype "passive"))
      (node (ref "U3") (pin "13") (pinfunction "A_13") (pintype "input"))
      (node (ref "U9") (pin "6") (pintype "output"))
    )
    (net (code "81") (name "Net-(U3F-Y)") (class "Default")
      (node (ref "P6") (pin "2") (pinfunction "2_2") (pintype "passive"))
      (node (ref "U3") (pin "12") (pinfunction "Y_12") (pintype "output"))
    )
    (net (code "82") (name "Net-(U4-Q0)") (class "Default")
      (node (ref "U4") (pin "15") (pinfunction "Q0_15") (pintype "tri_state"))
      (node (ref "U5") (pin "9") (pinfunction "A_9") (pintype "input"))
    )
    (net (code "83") (name "Net-(U4-Q1)") (class "Default")
      (node (ref "U4") (pin "1") (pinfunction "Q1_1") (pintype "tri_state"))
      (node (ref "U5") (pin "10") (pinfunction "B_10") (pintype "input"))
    )
    (net (code "84") (name "Net-(U4-Q2)") (class "Default")
      (node (ref "U4") (pin "2") (pinfunction "Q2_2") (pintype "tri_state"))
      (node (ref "U5") (pin "12") (pinfunction "C_12") (pintype "input"))
    )
    (net (code "85") (name "Net-(U4-Q5)") (class "Default")
      (node (ref "U4") (pin "5") (pinfunction "Q5_5") (pintype "tri_state"))
      (node (ref "U5") (pin "13") (pinfunction "D_13") (pintype "input"))
    )
    (net (code "86") (name "Net-(U6-QA)") (class "Default")
      (node (ref "R5") (pin "1") (pinfunction "1_1") (pintype "passive"))
      (node (ref "U6") (pin "13") (pinfunction "QA_13") (pintype "passive"))
    )
    (net (code "87") (name "Net-(U6-QB)") (class "Default")
      (node (ref "R6") (pin "1") (pinfunction "1_1") (pintype "passive"))
      (node (ref "U6") (pin "12") (pinfunction "QB_12") (pintype "passive"))
    )
    (net (code "88") (name "Net-(U6-QC)") (class "Default")
      (node (ref "R7") (pin "1") (pinfunction "1_1") (pintype "passive"))
      (node (ref "U6") (pin "11") (pinfunction "QC_11") (pintype "passive"))
    )
    (net (code "89") (name "Net-(U6-QD)") (class "Default")
      (node (ref "R8") (pin "1") (pinfunction "1_1") (pintype "passive"))
      (node (ref "U6") (pin "10") (pinfunction "QD_10") (pintype "passive"))
    )
    (net (code "90") (name "Net-(U6-QE)") (class "Default")
      (node (ref "R9") (pin "1") (pinfunction "1_1") (pintype "passive"))
      (node (ref "U6") (pin "9") (pinfunction "QE_9") (pintype "passive"))
    )
    (net (code "91") (name "Net-(U6-QF)") (class "Default")
      (node (ref "R10") (pin "1") (pinfunction "1_1") (pintype "passive"))
      (node (ref "U6") (pin "15") (pinfunction "QF_15") (pintype "passive"))
    )
    (net (code "92") (name "Net-(U6-QG)") (class "Default")
      (node (ref "R11") (pin "1") (pinfunction "1_1") (pintype "passive"))
      (node (ref "U6") (pin "14") (pinfunction "QG_14") (pintype "passive"))
    )
    (net (code "93") (name "Net-(U7-E3)") (class "Default")
      (node (ref "U14") (pin "12") (pintype "output"))
      (node (ref "U7") (pin "6") (pinfunction "E3_6") (pintype "input"))
    )
    (net (code "94") (name "Net-(U8-CCLR)") (class "Default")
      (node (ref "C5") (pin "1") (pinfunction "1_1") (pintype "passive"))
      (node (ref "P13") (pin "2") (pinfunction "2_2") (pintype "passive"))
      (node (ref "R14") (pin "1") (pinfunction "1_1") (pintype "passive"))
      (node (ref "U8") (pin "10") (pinfunction "CCLR_10") (pintype "input"))
    )
    (net (code "95") (name "Net-(U8-Q0)") (class "Default")
      (node (ref "U8") (pin "15") (pinfunction "Q0_15") (pintype "tri_state"))
      (node (ref "U9") (pin "3") (pintype "input"))
    )
    (net (code "96") (name "Net-(U8-Q3)") (class "Default")
      (node (ref "U8") (pin "3") (pinfunction "Q3_3") (pintype "tri_state"))
      (node (ref "U9") (pin "4") (pintype "input"))
    )
    (net (code "97") (name "Net-(U8-Q4)") (class "Default")
      (node (ref "U8") (pin "4") (pinfunction "Q4_4") (pintype "tri_state"))
      (node (ref "U9") (pin "5") (pintype "input"))
    )
    (net (code "98") (name "Net-(U10-1A1)") (class "Default")
      (node (ref "U10") (pin "2") (pinfunction "1A1_2") (pintype "input"))
      (node (ref "U17") (pin "2") (pinfunction "Q1_2") (pintype "output"))
    )
    (net (code "99") (name "Net-(U10-1A2)") (class "Default")
      (node (ref "U10") (pin "4") (pinfunction "1A2_4") (pintype "input"))
      (node (ref "U17") (pin "5") (pinfunction "Q2_5") (pintype "output"))
    )
    (net (code "100") (name "Net-(U10-1A3)") (class "Default")
      (node (ref "U10") (pin "6") (pinfunction "1A3_6") (pintype "input"))
      (node (ref "U17") (pin "6") (pinfunction "Q3_6") (pintype "output"))
    )
    (net (code "101") (name "Net-(U10-1A4)") (class "Default")
      (node (ref "U10") (pin "8") (pinfunction "1A4_8") (pintype "input"))
      (node (ref "U17") (pin "9") (pinfunction "Q4_9") (pintype "output"))
    )
    (net (code "102") (name "Net-(U10-2A1)") (class "Default")
      (node (ref "U10") (pin "11") (pinfunction "2A1_11") (pintype "input"))
      (node (ref "U17") (pin "12") (pinfunction "Q5_12") (pintype "output"))
    )
    (net (code "103") (name "Net-(U10-2A2)") (class "Default")
      (node (ref "U10") (pin "13") (pinfunction "2A2_13") (pintype "input"))
      (node (ref "U17") (pin "15") (pinfunction "Q6_15") (pintype "output"))
    )
    (net (code "104") (name "Net-(U10-2A3)") (class "Default")
      (node (ref "U10") (pin "15") (pinfunction "2A3_15") (pintype "input"))
      (node (ref "U17") (pin "16") (pinfunction "Q7_16") (pintype "output"))
    )
    (net (code "105") (name "Net-(U10-2A4)") (class "Default")
      (node (ref "U10") (pin "17") (pinfunction "2A4_17") (pintype "input"))
      (node (ref "U17") (pin "19") (pinfunction "Q8_19") (pintype "output"))
    )
    (net (code "106") (name "Net-(U11-1A1)") (class "Default")
      (node (ref "U11") (pin "2") (pinfunction "1A1_2") (pintype "input"))
      (node (ref "U18") (pin "2") (pinfunction "Q1_2") (pintype "output"))
    )
    (net (code "107") (name "Net-(U11-1A2)") (class "Default")
      (node (ref "U11") (pin "4") (pinfunction "1A2_4") (pintype "input"))
      (node (ref "U18") (pin "5") (pinfunction "Q2_5") (pintype "output"))
    )
    (net (code "108") (name "Net-(U11-1A3)") (class "Default")
      (node (ref "U11") (pin "6") (pinfunction "1A3_6") (pintype "input"))
      (node (ref "U18") (pin "6") (pinfunction "Q3_6") (pintype "output"))
    )
    (net (code "109") (name "Net-(U11-1A4)") (class "Default")
      (node (ref "U11") (pin "8") (pinfunction "1A4_8") (pintype "input"))
      (node (ref "U18") (pin "9") (pinfunction "Q4_9") (pintype "output"))
    )
    (net (code "110") (name "Net-(U11-2A1)") (class "Default")
      (node (ref "U11") (pin "11") (pinfunction "2A1_11") (pintype "input"))
      (node (ref "U18") (pin "12") (pinfunction "Q5_12") (pintype "output"))
    )
    (net (code "111") (name "Net-(U11-2A2)") (class "Default")
      (node (ref "U11") (pin "13") (pinfunction "2A2_13") (pintype "input"))
      (node (ref "U18") (pin "15") (pinfunction "Q6_15") (pintype "output"))
    )
    (net (code "112") (name "Net-(U11-2A3)") (class "Default")
      (node (ref "U11") (pin "15") (pinfunction "2A3_15") (pintype "input"))
      (node (ref "U18") (pin "16") (pinfunction "Q7_16") (pintype "output"))
    )
    (net (code "113") (name "Net-(U11-2A4)") (class "Default")
      (node (ref "U11") (pin "17") (pinfunction "2A4_17") (pintype "input"))
      (node (ref "U18") (pin "19") (pinfunction "Q8_19") (pintype "output"))
    )
    (net (code "114") (name "Net-(U12-1A1)") (class "Default")
      (node (ref "U12") (pin "2") (pinfunction "1A1_2") (pintype "input"))
      (node (ref "U19") (pin "2") (pinfunction "Q1_2") (pintype "output"))
    )
    (net (code "115") (name "Net-(U12-1A2)") (class "Default")
      (node (ref "U12") (pin "4") (pinfunction "1A2_4") (pintype "input"))
      (node (ref "U19") (pin "5") (pinfunction "Q2_5") (pintype "output"))
    )
    (net (code "116") (name "Net-(U12-1A3)") (class "Default")
      (node (ref "U12") (pin "6") (pinfunction "1A3_6") (pintype "input"))
      (node (ref "U19") (pin "6") (pinfunction "Q3_6") (pintype "output"))
    )
    (net (code "117") (name "Net-(U12-1A4)") (class "Default")
      (node (ref "U12") (pin "8") (pinfunction "1A4_8") (pintype "input"))
      (node (ref "U19") (pin "9") (pinfunction "Q4_9") (pintype "output"))
    )
    (net (code "118") (name "Net-(U12-2A1)") (class "Default")
      (node (ref "U12") (pin "11") (pinfunction "2A1_11") (pintype "input"))
      (node (ref "U19") (pin "12") (pinfunction "Q5_12") (pintype "output"))
    )
    (net (code "119") (name "Net-(U12-2A2)") (class "Default")
      (node (ref "U12") (pin "13") (pinfunction "2A2_13") (pintype "input"))
      (node (ref "U19") (pin "15") (pinfunction "Q6_15") (pintype "output"))
    )
    (net (code "120") (name "Net-(U12-2A3)") (class "Default")
      (node (ref "U12") (pin "15") (pinfunction "2A3_15") (pintype "input"))
      (node (ref "U19") (pin "16") (pinfunction "Q7_16") (pintype "output"))
    )
    (net (code "121") (name "Net-(U12-2A4)") (class "Default")
      (node (ref "U12") (pin "17") (pinfunction "2A4_17") (pintype "input"))
      (node (ref "U19") (pin "19") (pinfunction "Q8_19") (pintype "output"))
    )
    (net (code "122") (name "Net-(U13-1R)") (class "Default")
      (node (ref "P13") (pin "1") (pinfunction "1_1") (pintype "passive"))
      (node (ref "U13") (pin "1") (pinfunction "1R_1") (pintype "input"))
      (node (ref "U13") (pin "10") (pinfunction "3R_10") (pintype "input"))
      (node (ref "U13") (pin "14") (pinfunction "4R_14") (pintype "input"))
      (node (ref "U13") (pin "5") (pinfunction "2R_5") (pintype "input"))
    )
    (net (code "123") (name "Net-(U13-1S1)") (class "Default")
      (node (ref "U13") (pin "2") (pinfunction "1S1_2") (pintype "input"))
      (node (ref "U13") (pin "3") (pinfunction "1S2_3") (pintype "input"))
      (node (ref "U14") (pin "4") (pintype "output"))
    )
    (net (code "124") (name "Net-(U13-2S)") (class "Default")
      (node (ref "U13") (pin "6") (pinfunction "2S_6") (pintype "input"))
      (node (ref "U14") (pin "6") (pintype "output"))
    )
    (net (code "125") (name "Net-(U13-3S1)") (class "Default")
      (node (ref "U13") (pin "11") (pinfunction "3S1_11") (pintype "input"))
      (node (ref "U13") (pin "12") (pinfunction "3S2_12") (pintype "input"))
      (node (ref "U14") (pin "8") (pintype "output"))
    )
    (net (code "126") (name "Net-(U13-4S)") (class "Default")
      (node (ref "U13") (pin "15") (pinfunction "4S_15") (pintype "input"))
      (node (ref "U14") (pin "10") (pintype "output"))
    )
    (net (code "127") (name "Net-(U13-Q1)") (class "Default")
      (node (ref "U13") (pin "4") (pinfunction "Q1_4") (pintype "output"))
      (node (ref "U15") (pin "3") (pinfunction "D1_3") (pintype "input"))
    )
    (net (code "128") (name "Net-(U13-Q2)") (class "Default")
      (node (ref "U13") (pin "7") (pinfunction "Q2_7") (pintype "output"))
      (node (ref "U15") (pin "4") (pinfunction "D2_4") (pintype "input"))
    )
    (net (code "129") (name "Net-(U13-Q3)") (class "Default")
      (node (ref "U13") (pin "9") (pinfunction "Q3_9") (pintype "output"))
      (node (ref "U15") (pin "7") (pinfunction "D3_7") (pintype "input"))
    )
    (net (code "130") (name "Net-(U13-Q4)") (class "Default")
      (node (ref "U13") (pin "13") (pinfunction "Q4_13") (pintype "output"))
      (node (ref "U15") (pin "8") (pinfunction "D4_8") (pintype "input"))
    )
    (net (code "131") (name "Net-(U15-Q1)") (class "Default")
      (node (ref "U15") (pin "2") (pinfunction "Q1_2") (pintype "output"))
      (node (ref "U16") (pin "4") (pinfunction "I0_4") (pintype "input"))
    )
    (net (code "132") (name "Net-(U15-Q2)") (class "Default")
      (node (ref "U15") (pin "5") (pinfunction "Q2_5") (pintype "output"))
      (node (ref "U16") (pin "3") (pinfunction "I1_3") (pintype "input"))
    )
    (net (code "133") (name "Net-(U15-Q3)") (class "Default")
      (node (ref "U15") (pin "6") (pinfunction "Q3_6") (pintype "output"))
      (node (ref "U16") (pin "2") (pinfunction "I2_2") (pintype "input"))
    )
    (net (code "134") (name "Net-(U15-Q4)") (class "Default")
      (node (ref "U15") (pin "9") (pinfunction "Q4_9") (pintype "output"))
      (node (ref "U16") (pin "1") (pinfunction "I3_1") (pintype "input"))
    )
    (net (code "135") (name "Net-(U16-Z)") (class "Default")
      (node (ref "P14") (pin "1") (pinfunction "1_1") (pintype "passive"))
      (node (ref "U16") (pin "5") (pinfunction "Z_5") (pintype "output"))
    )
    (net (code "136") (name "Net-(U17-D1)") (class "Default")
      (node (ref "U17") (pin "3") (pinfunction "D1_3") (pintype "input"))
      (node (ref "U20") (pin "3") (pinfunction "Q0_3") (pintype "output"))
    )
    (net (code "137") (name "Net-(U17-D2)") (class "Default")
      (node (ref "U17") (pin "4") (pinfunction "D2_4") (pintype "input"))
      (node (ref "U20") (pin "4") (pinfunction "Q1_4") (pintype "output"))
    )
    (net (code "138") (name "Net-(U17-D3)") (class "Default")
      (node (ref "U17") (pin "7") (pinfunction "D3_7") (pintype "input"))
      (node (ref "U20") (pin "5") (pinfunction "Q2_5") (pintype "output"))
    )
    (net (code "139") (name "Net-(U17-D4)") (class "Default")
      (node (ref "U17") (pin "8") (pinfunction "D4_8") (pintype "input"))
      (node (ref "U20") (pin "6") (pinfunction "Q3_6") (pintype "output"))
    )
    (net (code "140") (name "Net-(U17-D6)") (class "Default")
      (node (ref "U17") (pin "14") (pinfunction "D6_14") (pintype "input"))
      (node (ref "U20") (pin "12") (pinfunction "Q1_12") (pintype "output"))
    )
    (net (code "141") (name "Net-(U17-D7)") (class "Default")
      (node (ref "U17") (pin "17") (pinfunction "D7_17") (pintype "input"))
      (node (ref "U20") (pin "13") (pinfunction "Q2_13") (pintype "output"))
    )
    (net (code "142") (name "Net-(U18-D2)") (class "Default")
      (node (ref "U18") (pin "4") (pinfunction "D2_4") (pintype "input"))
      (node (ref "U21") (pin "4") (pinfunction "Q1_4") (pintype "output"))
    )
    (net (code "143") (name "Net-(U18-D3)") (class "Default")
      (node (ref "U18") (pin "7") (pinfunction "D3_7") (pintype "input"))
      (node (ref "U21") (pin "5") (pinfunction "Q2_5") (pintype "output"))
    )
    (net (code "144") (name "Net-(U18-D6)") (class "Default")
      (node (ref "U18") (pin "14") (pinfunction "D6_14") (pintype "input"))
      (node (ref "U21") (pin "12") (pinfunction "Q1_12") (pintype "output"))
    )
    (net (code "145") (name "Net-(U18-D7)") (class "Default")
      (node (ref "U18") (pin "17") (pinfunction "D7_17") (pintype "input"))
      (node (ref "U21") (pin "13") (pinfunction "Q2_13") (pintype "output"))
    )
    (net (code "146") (name "Net-(U19-D2)") (class "Default")
      (node (ref "U19") (pin "4") (pinfunction "D2_4") (pintype "input"))
      (node (ref "U22") (pin "4") (pinfunction "Q1_4") (pintype "output"))
    )
    (net (code "147") (name "Net-(U19-D3)") (class "Default")
      (node (ref "U19") (pin "7") (pinfunction "D3_7") (pintype "input"))
      (node (ref "U22") (pin "5") (pinfunction "Q2_5") (pintype "output"))
    )
    (net (code "148") (name "Net-(U19-D6)") (class "Default")
      (node (ref "U19") (pin "14") (pinfunction "D6_14") (pintype "input"))
      (node (ref "U22") (pin "12") (pinfunction "Q1_12") (pintype "output"))
    )
    (net (code "149") (name "Net-(U19-D7)") (class "Default")
      (node (ref "U19") (pin "17") (pinfunction "D7_17") (pintype "input"))
      (node (ref "U22") (pin "13") (pinfunction "Q2_13") (pintype "output"))
    )
    (net (code "150") (name "Net-(U22A-CLK)") (class "Default")
      (node (ref "C10") (pin "2") (pinfunction "2_2") (pintype "passive"))
      (node (ref "R18") (pin "2") (pinfunction "2_2") (pintype "passive"))
      (node (ref "U22") (pin "1") (pinfunction "CLK_1") (pintype "input"))
    )
    (net (code "151") (name "Net-(U22B-CLK)") (class "Default")
      (node (ref "U14") (pin "2") (pintype "output"))
      (node (ref "U22") (pin "9") (pinfunction "CLK_9") (pintype "input"))
    )
    (net (code "152") (name "Net-(U23-FB)") (class "Default")
      (node (ref "R16") (pin "2") (pinfunction "2_2") (pintype "passive"))
      (node (ref "R17") (pin "1") (pinfunction "1_1") (pintype "passive"))
      (node (ref "U23") (pin "6") (pinfunction "FB_6") (pintype "passive"))
    )
    (net (code "153") (name "Net-(U23-LX)") (class "Default")
      (node (ref "D1") (pin "A") (pinfunction "A_A") (pintype "passive"))
      (node (ref "L1") (pin "2") (pintype "passive"))
      (node (ref "U23") (pin "4") (pinfunction "LX_4") (pintype "passive"))
    )
    (net (code "154") (name "Net-(V1-+)") (class "Default")
      (node (ref "K1") (pin "1") (pinfunction "1_1") (pintype "passive"))
      (node (ref "V1") (pin "1") (pinfunction "+_1") (pintype "passive"))
    )
    (net (code "155") (name "VCC") (class "Default")
      (node (ref "C7") (pin "A") (pinfunction "1_A") (pintype "passive"))
      (node (ref "D14") (pin "A") (pinfunction "1_A") (pintype "passive"))
      (node (ref "D2") (pin "K") (pinfunction "K_K") (pintype "passive"))
      (node (ref "P12") (pin "1") (pinfunction "1_1") (pintype "passive"))
      (node (ref "T1") (pin "2") (pinfunction "2_2") (pintype "passive"))
    )
    (net (code "156") (name "VDD") (class "Default")
      (node (ref "C13") (pin "2") (pinfunction "2_2") (pintype "passive"))
      (node (ref "P2") (pin "17") (pinfunction "17_17") (pintype "passive"))
      (node (ref "P2") (pin "18") (pinfunction "18_18") (pintype "passive"))
      (node (ref "P2") (pin "19") (pinfunction "19_19") (pintype "passive"))
      (node (ref "P2") (pin "20") (pinfunction "20_20") (pintype "passive"))
      (node (ref "P2") (pin "21") (pinfunction "21_21") (pintype "passive"))
      (node (ref "P2") (pin "22") (pinfunction "22_22") (pintype "passive"))
      (node (ref "P2") (pin "23") (pinfunction "23_23") (pintype "passive"))
      (node (ref "P2") (pin "24") (pinfunction "24_24") (pintype "passive"))
      (node (ref "P7") (pin "2") (pinfunction "2_2") (pintype "passive"))
      (node (ref "R12") (pin "2") (pinfunction "2_2") (pintype "passive"))
      (node (ref "T3") (pin "1") (pinfunction "1_1") (pintype "passive"))
      (node (ref "T4") (pin "2") (pinfunction "2_2") (pintype "passive"))
      (node (ref "T5") (pin "1") (pinfunction "1_1") (pintype "passive"))
      (node (ref "T6") (pin "2") (pinfunction "2_2") (pintype "passive"))
      (node (ref "U2") (pin "14") (pinfunction "VCC_14") (pintype "power_in"))
    )
    (net (code "157") (name "VDD1") (class "Default")
      (node (ref "C11") (pin "2") (pinfunction "2_2") (pintype "passive"))
      (node (ref "P8") (pin "2") (pinfunction "2_2") (pintype "passive"))
      (node (ref "R13") (pin "2") (pinfunction "2_2") (pintype "passive"))
    )
    (net (code "158") (name "VDD2") (class "Default")
      (node (ref "C12") (pin "2") (pinfunction "2_2") (pintype "passive"))
      (node (ref "P9") (pin "2") (pinfunction "2_2") (pintype "passive"))
      (node (ref "R15") (pin "2") (pinfunction "2_2") (pintype "passive"))
    )
    (net (code "159") (name "VDD3") (class "Default")
      (node (ref "C14") (pin "2") (pinfunction "2_2") (pintype "passive"))
      (node (ref "P10") (pin "2") (pinfunction "2_2") (pintype "passive"))
      (node (ref "R19") (pin "2") (pinfunction "2_2") (pintype "passive"))
      (node (ref "U15") (pin "20") (pinfunction "VDD_20") (pintype "power_in"))
      (node (ref "U16") (pin "14") (pinfunction "I5_14") (pintype "input"))
      (node (ref "U16") (pin "15") (pinfunction "I4_15") (pintype "input"))
    )
    (net (code "160") (name "VDD4") (class "Default")
      (node (ref "C15") (pin "2") (pinfunction "2_2") (pintype "passive"))
      (node (ref "P11") (pin "2") (pinfunction "2_2") (pintype "passive"))
      (node (ref "R20") (pin "2") (pinfunction "2_2") (pintype "passive"))
      (node (ref "U10") (pin "20") (pinfunction "VDD_20") (pintype "power_in"))
      (node (ref "U11") (pin "20") (pinfunction "VDD_20") (pintype "power_in"))
      (node (ref "U12") (pin "20") (pinfunction "VDD_20") (pintype "power_in"))
      (node (ref "U17") (pin "20") (pinfunction "VDD_20") (pintype "power_in"))
      (node (ref "U18") (pin "20") (pinfunction "VDD_20") (pintype "power_in"))
      (node (ref "U19") (pin "20") (pinfunction "VDD_20") (pintype "power_in"))
      (node (ref "U6") (pin "16") (pinfunction "VDD_16") (pintype "power_in"))
      (node (ref "U7") (pin "16") (pinfunction "VDD_16") (pintype "power_in"))
    )
    (net (code "161") (name "unconnected-(R2-Pad1)") (class "Default")
      (node (ref "R2") (pin "1") (pinfunction "1_1") (pintype "passive+no_connect"))
    )
    (net (code "162") (name "unconnected-(T7-Pad2)") (class "Default")
      (node (ref "T7") (pin "2") (pinfunction "2_2") (pintype "passive"))
    )
    (net (code "163") (name "unconnected-(U1-DP-Pad3)") (class "Default")
      (node (ref "U1") (pin "3") (pinfunction "DP_3") (pintype "passive+no_connect"))
    )
    (net (code "164") (name "unconnected-(U2B-Q0-Pad11)") (class "Default")
      (node (ref "U2") (pin "11") (pinfunction "Q0_11") (pintype "output+no_connect"))
    )
    (net (code "165") (name "unconnected-(U2B-Q3-Pad8)") (class "Default")
      (node (ref "U2") (pin "8") (pinfunction "Q3_8") (pintype "output+no_connect"))
    )
    (net (code "166") (name "unconnected-(U4-Q3-Pad3)") (class "Default")
      (node (ref "U4") (pin "3") (pinfunction "Q3_3") (pintype "tri_state+no_connect"))
    )
    (net (code "167") (name "unconnected-(U4-Q4-Pad4)") (class "Default")
      (node (ref "U4") (pin "4") (pinfunction "Q4_4") (pintype "tri_state+no_connect"))
    )
    (net (code "168") (name "unconnected-(U4-Q6-Pad6)") (class "Default")
      (node (ref "U4") (pin "6") (pinfunction "Q6_6") (pintype "tri_state+no_connect"))
    )
    (net (code "169") (name "unconnected-(U4-Q7-Pad7)") (class "Default")
      (node (ref "U4") (pin "7") (pinfunction "Q7_7") (pintype "tri_state+no_connect"))
    )
    (net (code "170") (name "unconnected-(U4-~{RCO}-Pad9)") (class "Default")
      (node (ref "U4") (pin "9") (pinfunction "~{RCO}_9") (pintype "output+no_connect"))
    )
    (net (code "171") (name "unconnected-(U7-Y6-Pad9)") (class "Default")
      (node (ref "U7") (pin "9") (pinfunction "Y6_9") (pintype "output+no_connect"))
    )
    (net (code "172") (name "unconnected-(U7-Y7-Pad7)") (class "Default")
      (node (ref "U7") (pin "7") (pinfunction "Y7_7") (pintype "output+no_connect"))
    )
    (net (code "173") (name "unconnected-(U8-Q1-Pad1)") (class "Default")
      (node (ref "U8") (pin "1") (pinfunction "Q1_1") (pintype "tri_state+no_connect"))
    )
    (net (code "174") (name "unconnected-(U8-Q2-Pad2)") (class "Default")
      (node (ref "U8") (pin "2") (pinfunction "Q2_2") (pintype "tri_state+no_connect"))
    )
    (net (code "175") (name "unconnected-(U8-Q5-Pad5)") (class "Default")
      (node (ref "U8") (pin "5") (pinfunction "Q5_5") (pintype "tri_state+no_connect"))
    )
    (net (code "176") (name "unconnected-(U8-Q6-Pad6)") (class "Default")
      (node (ref "U8") (pin "6") (pinfunction "Q6_6") (pintype "tri_state+no_connect"))
    )
    (net (code "177") (name "unconnected-(U8-Q7-Pad7)") (class "Default")
      (node (ref "U8") (pin "7") (pinfunction "Q7_7") (pintype "tri_state+no_connect"))
    )
    (net (code "178") (name "unconnected-(U8-~{RCO}-Pad9)") (class "Default")
      (node (ref "U8") (pin "9") (pinfunction "~{RCO}_9") (pintype "output+no_connect"))
    )
    (net (code "179") (name "unconnected-(U15-D5-Pad13)") (class "Default")
      (node (ref "U15") (pin "13") (pinfunction "D5_13") (pintype "input+no_connect"))
    )
    (net (code "180") (name "unconnected-(U15-D6-Pad14)") (class "Default")
      (node (ref "U15") (pin "14") (pinfunction "D6_14") (pintype "input+no_connect"))
    )
    (net (code "181") (name "unconnected-(U15-D7-Pad17)") (class "Default")
      (node (ref "U15") (pin "17") (pinfunction "D7_17") (pintype "input+no_connect"))
    )
    (net (code "182") (name "unconnected-(U15-D8-Pad18)") (class "Default")
      (node (ref "U15") (pin "18") (pinfunction "D8_18") (pintype "input+no_connect"))
    )
    (net (code "183") (name "unconnected-(U15-Q5-Pad12)") (class "Default")
      (node (ref "U15") (pin "12") (pinfunction "Q5_12") (pintype "output"))
    )
    (net (code "184") (name "unconnected-(U15-Q6-Pad15)") (class "Default")
      (node (ref "U15") (pin "15") (pinfunction "Q6_15") (pintype "output"))
    )
    (net (code "185") (name "unconnected-(U15-Q7-Pad16)") (class "Default")
      (node (ref "U15") (pin "16") (pinfunction "Q7_16") (pintype "output"))
    )
    (net (code "186") (name "unconnected-(U15-Q8-Pad19)") (class "Default")
      (node (ref "U15") (pin "19") (pinfunction "Q8_19") (pintype "output"))
    )
    (net (code "187") (name "unconnected-(U16-~{Z}-Pad6)") (class "Default")
      (node (ref "U16") (pin "6") (pinfunction "~{Z}_6") (pintype "output"))
    )
    (net (code "188") (name "unconnected-(U23-EXT-Pad2)") (class "Default")
      (node (ref "U23") (pin "2") (pinfunction "EXT_2") (pintype "passive+no_connect"))
    )
  )
)
